# untitled.net
KiCad netlist of a schematic drawn in EAGLE
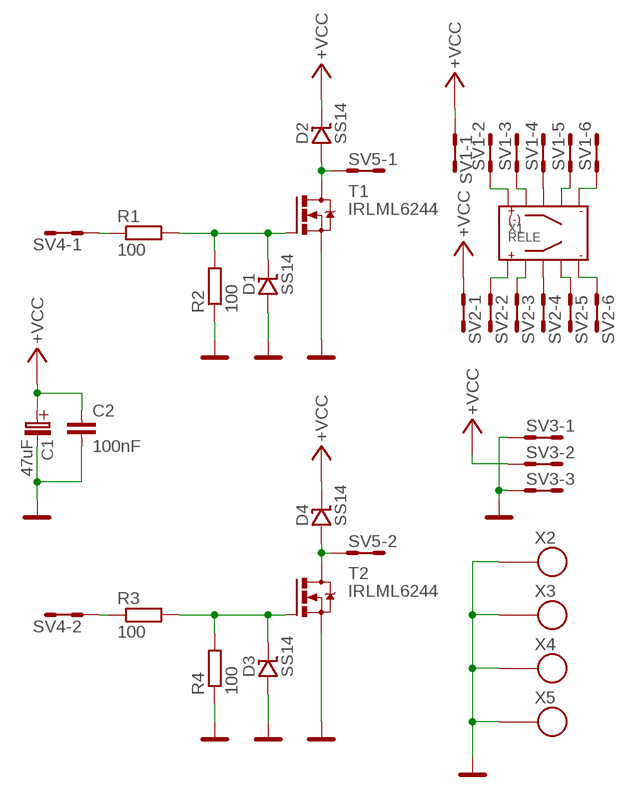
[diagram p0: schematic, sheet 1]

(export (version "E")
  (design (tool "Eeschema 10.0.6"))
  (components
    (comp (ref "C1") (value "47uF") (footprint "eagle-import:B") (libsource (lib "eagle-import") (part "B")))
    (comp (ref "C2")
      (value "100nF")
      (footprint "eagle-import:C0805")
      (libsource (lib "eagle-import") (part "C0805"))
    )
    (comp (ref "D1")
      (value "SS14")
      (footprint "eagle-import:SMA")
      (libsource (lib "eagle-import") (part "D-SHOTKY-SMA"))
    )
    (comp (ref "D2")
      (value "SS14")
      (footprint "eagle-import:SMA")
      (libsource (lib "eagle-import") (part "D-SHOTKY-SMA"))
    )
    (comp (ref "D3")
      (value "SS14")
      (footprint "eagle-import:SMA")
      (libsource (lib "eagle-import") (part "D-SHOTKY-SMA"))
    )
    (comp (ref "D4")
      (value "SS14")
      (footprint "eagle-import:SMA")
      (libsource (lib "eagle-import") (part "D-SHOTKY-SMA"))
    )
    (comp (ref "R1")
      (value "100")
      (footprint "eagle-import:0805")
      (libsource (lib "eagle-import") (part "R0805"))
    )
    (comp (ref "R2")
      (value "100")
      (footprint "eagle-import:0805")
      (libsource (lib "eagle-import") (part "R0805"))
    )
    (comp (ref "R3")
      (value "100")
      (footprint "eagle-import:0805")
      (libsource (lib "eagle-import") (part "R0805"))
    )
    (comp (ref "R4")
      (value "100")
      (footprint "eagle-import:0805")
      (libsource (lib "eagle-import") (part "R0805"))
    )
    (comp (ref "SV1")
      (value "MA06-2")
      (footprint "eagle-import:MA06-2")
      (libsource (lib "eagle-import") (part "MA06-2"))
    )
    (comp (ref "SV2")
      (value "MA06-2")
      (footprint "eagle-import:MA06-2")
      (libsource (lib "eagle-import") (part "MA06-2"))
    )
    (comp (ref "SV3")
      (value "MA03-2")
      (footprint "eagle-import:MA03-2")
      (libsource (lib "eagle-import") (part "MA03-2"))
    )
    (comp (ref "SV4")
      (value "MA02-2")
      (footprint "eagle-import:MA02-2")
      (libsource (lib "eagle-import") (part "MA02-2"))
    )
    (comp (ref "SV5")
      (value "MA02-2")
      (footprint "eagle-import:MA02-2")
      (libsource (lib "eagle-import") (part "MA02-2"))
    )
    (comp (ref "T1")
      (value "IRLML6244")
      (footprint "eagle-import:SOT23")
      (libsource (lib "eagle-import") (part "IRLML6244TRPBF"))
    )
    (comp (ref "T2")
      (value "IRLML6244")
      (footprint "eagle-import:SOT23")
      (libsource (lib "eagle-import") (part "IRLML6244TRPBF"))
    )
    (comp (ref "X1")
      (value "RELE")
      (footprint "eagle-import:RELE")
      (libsource (lib "eagle-import") (part "RELE"))
    )
    (comp (ref "X2")
      (value "SROUB3M")
      (footprint "eagle-import:SROUB3M")
      (libsource (lib "eagle-import") (part "SROUB3M"))
    )
    (comp (ref "X3")
      (value "SROUB3M")
      (footprint "eagle-import:SROUB3M")
      (libsource (lib "eagle-import") (part "SROUB3M"))
    )
    (comp (ref "X4")
      (value "SROUB3M")
      (footprint "eagle-import:SROUB3M")
      (libsource (lib "eagle-import") (part "SROUB3M"))
    )
    (comp (ref "X5")
      (value "SROUB3M")
      (footprint "eagle-import:SROUB3M")
      (libsource (lib "eagle-import") (part "SROUB3M"))
    )
  )
  (nets
    (net (code "1") (name "+VCC") (class "Default")
      (node (ref "C1") (pin "+") (pinfunction "C_EL+_+") (pintype "passive"))
      (node (ref "C2") (pin "1") (pinfunction "1_1") (pintype "passive"))
      (node (ref "D2") (pin "K") (pinfunction "K_K") (pintype "passive"))
      (node (ref "D4") (pin "K") (pinfunction "K_K") (pintype "passive"))
      (node (ref "SV1") (pin "1") (pinfunction "K_1") (pintype "passive"))
      (node (ref "SV1") (pin "2") (pinfunction "K_2") (pintype "passive"))
      (node (ref "SV2") (pin "1") (pinfunction "K_1") (pintype "passive"))
      (node (ref "SV2") (pin "2") (pinfunction "K_2") (pintype "passive"))
      (node (ref "SV3") (pin "3") (pinfunction "K_3") (pintype "passive"))
      (node (ref "SV3") (pin "4") (pinfunction "K_4") (pintype "passive"))
    )
    (net (code "2") (name "GND") (class "Default")
      (node (ref "C1") (pin "-") (pinfunction "C_EL-_-") (pintype "passive"))
      (node (ref "C2") (pin "2") (pinfunction "2_2") (pintype "passive"))
      (node (ref "D1") (pin "A") (pinfunction "A_A") (pintype "passive"))
      (node (ref "D3") (pin "A") (pinfunction "A_A") (pintype "passive"))
      (node (ref "R2") (pin "1") (pinfunction "1_1") (pintype "passive"))
      (node (ref "R4") (pin "1") (pinfunction "1_1") (pintype "passive"))
      (node (ref "SV3") (pin "1") (pinfunction "K_1") (pintype "passive"))
      (node (ref "SV3") (pin "2") (pinfunction "K_2") (pintype "passive"))
      (node (ref "SV3") (pin "5") (pinfunction "K_5") (pintype "passive"))
      (node (ref "SV3") (pin "6") (pinfunction "K_6") (pintype "passive"))
      (node (ref "T1") (pin "2") (pinfunction "S_2") (pintype "passive"))
      (node (ref "T2") (pin "2") (pinfunction "S_2") (pintype "passive"))
      (node (ref "X2") (pin "P$1") (pinfunction "P$1_P$1") (pintype "bidirectional"))
      (node (ref "X3") (pin "P$1") (pinfunction "P$1_P$1") (pintype "bidirectional"))
      (node (ref "X4") (pin "P$1") (pinfunction "P$1_P$1") (pintype "bidirectional"))
      (node (ref "X5") (pin "P$1") (pinfunction "P$1_P$1") (pintype "bidirectional"))
    )
    (net (code "3") (name "Net-(R1-Pad1)") (class "Default")
      (node (ref "R1") (pin "1") (pinfunction "1_1") (pintype "passive"))
      (node (ref "SV4") (pin "1") (pinfunction "K_1") (pintype "passive"))
      (node (ref "SV4") (pin "2") (pinfunction "K_2") (pintype "passive"))
    )
    (net (code "4") (name "Net-(R3-Pad1)") (class "Default")
      (node (ref "R3") (pin "1") (pinfunction "1_1") (pintype "passive"))
      (node (ref "SV4") (pin "3") (pinfunction "K_3") (pintype "passive"))
      (node (ref "SV4") (pin "4") (pinfunction "K_4") (pintype "passive"))
    )
    (net (code "5") (name "Net-(T1-D)") (class "Default")
      (node (ref "D2") (pin "A") (pinfunction "A_A") (pintype "passive"))
      (node (ref "SV5") (pin "1") (pinfunction "K_1") (pintype "passive"))
      (node (ref "SV5") (pin "2") (pinfunction "K_2") (pintype "passive"))
      (node (ref "T1") (pin "3") (pinfunction "D_3") (pintype "passive"))
    )
    (net (code "6") (name "Net-(T1-G)") (class "Default")
      (node (ref "D1") (pin "K") (pinfunction "K_K") (pintype "passive"))
      (node (ref "R1") (pin "2") (pinfunction "2_2") (pintype "passive"))
      (node (ref "R2") (pin "2") (pinfunction "2_2") (pintype "passive"))
      (node (ref "T1") (pin "1") (pinfunction "G_1") (pintype "passive"))
    )
    (net (code "7") (name "Net-(T2-D)") (class "Default")
      (node (ref "D4") (pin "A") (pinfunction "A_A") (pintype "passive"))
      (node (ref "SV5") (pin "3") (pinfunction "K_3") (pintype "passive"))
      (node (ref "SV5") (pin "4") (pinfunction "K_4") (pintype "passive"))
      (node (ref "T2") (pin "3") (pinfunction "D_3") (pintype "passive"))
    )
    (net (code "8") (name "Net-(T2-G)") (class "Default")
      (node (ref "D3") (pin "K") (pinfunction "K_K") (pintype "passive"))
      (node (ref "R3") (pin "2") (pinfunction "2_2") (pintype "passive"))
      (node (ref "R4") (pin "2") (pinfunction "2_2") (pintype "passive"))
      (node (ref "T2") (pin "1") (pinfunction "G_1") (pintype "passive"))
    )
    (net (code "9") (name "Net-(X1-P$1)") (class "Default")
      (node (ref "SV2") (pin "3") (pinfunction "K_3") (pintype "passive"))
      (node (ref "SV2") (pin "4") (pinfunction "K_4") (pintype "passive"))
      (node (ref "X1") (pin "1") (pinfunction "P$1_1") (pintype "passive"))
    )
    (net (code "10") (name "Net-(X1-P$2)") (class "Default")
      (node (ref "SV2") (pin "5") (pinfunction "K_5") (pintype "passive"))
      (node (ref "SV2") (pin "6") (pinfunction "K_6") (pintype "passive"))
      (node (ref "X1") (pin "2") (pinfunction "P$2_2") (pintype "passive"))
    )
    (net (code "11") (name "Net-(X1-P$3)") (class "Default")
      (node (ref "SV2") (pin "7") (pinfunction "K_7") (pintype "passive"))
      (node (ref "SV2") (pin "8") (pinfunction "K_8") (pintype "passive"))
      (node (ref "X1") (pin "3") (pinfunction "P$3_3") (pintype "passive"))
    )
    (net (code "12") (name "Net-(X1-P$4)") (class "Default")
      (node (ref "SV2") (pin "10") (pinfunction "K_10") (pintype "passive"))
      (node (ref "SV2") (pin "9") (pinfunction "K_9") (pintype "passive"))
      (node (ref "X1") (pin "4") (pinfunction "P$4_4") (pintype "passive"))
    )
    (net (code "13") (name "Net-(X1-P$5)") (class "Default")
      (node (ref "SV2") (pin "11") (pinfunction "K_11") (pintype "passive"))
      (node (ref "SV2") (pin "12") (pinfunction "K_12") (pintype "passive"))
      (node (ref "X1") (pin "5") (pinfunction "P$5_5") (pintype "passive"))
    )
    (net (code "14") (name "Net-(X1-P$6)") (class "Default")
      (node (ref "SV1") (pin "11") (pinfunction "K_11") (pintype "passive"))
      (node (ref "SV1") (pin "12") (pinfunction "K_12") (pintype "passive"))
      (node (ref "X1") (pin "6") (pinfunction "P$6_6") (pintype "passive"))
    )
    (net (code "15") (name "Net-(X1-P$7)") (class "Default")
      (node (ref "SV1") (pin "10") (pinfunction "K_10") (pintype "passive"))
      (node (ref "SV1") (pin "9") (pinfunction "K_9") (pintype "passive"))
      (node (ref "X1") (pin "7") (pinfunction "P$7_7") (pintype "passive"))
    )
    (net (code "16") (name "Net-(X1-P$8)") (class "Default")
      (node (ref "SV1") (pin "7") (pinfunction "K_7") (pintype "passive"))
      (node (ref "SV1") (pin "8") (pinfunction "K_8") (pintype "passive"))
      (node (ref "X1") (pin "8") (pinfunction "P$8_8") (pintype "passive"))
    )
    (net (code "17") (name "Net-(X1-P$9)") (class "Default")
      (node (ref "SV1") (pin "5") (pinfunction "K_5") (pintype "passive"))
      (node (ref "SV1") (pin "6") (pinfunction "K_6") (pintype "passive"))
      (node (ref "X1") (pin "9") (pinfunction "P$9_9") (pintype "passive"))
    )
    (net (code "18") (name "Net-(X1-P$10)") (class "Default")
      (node (ref "SV1") (pin "3") (pinfunction "K_3") (pintype "passive"))
      (node (ref "SV1") (pin "4") (pinfunction "K_4") (pintype "passive"))
      (node (ref "X1") (pin "10") (pinfunction "P$10_10") (pintype "passive"))
    )
  )
)
